# untitled.net
KiCad netlist of a schematic drawn in EAGLE
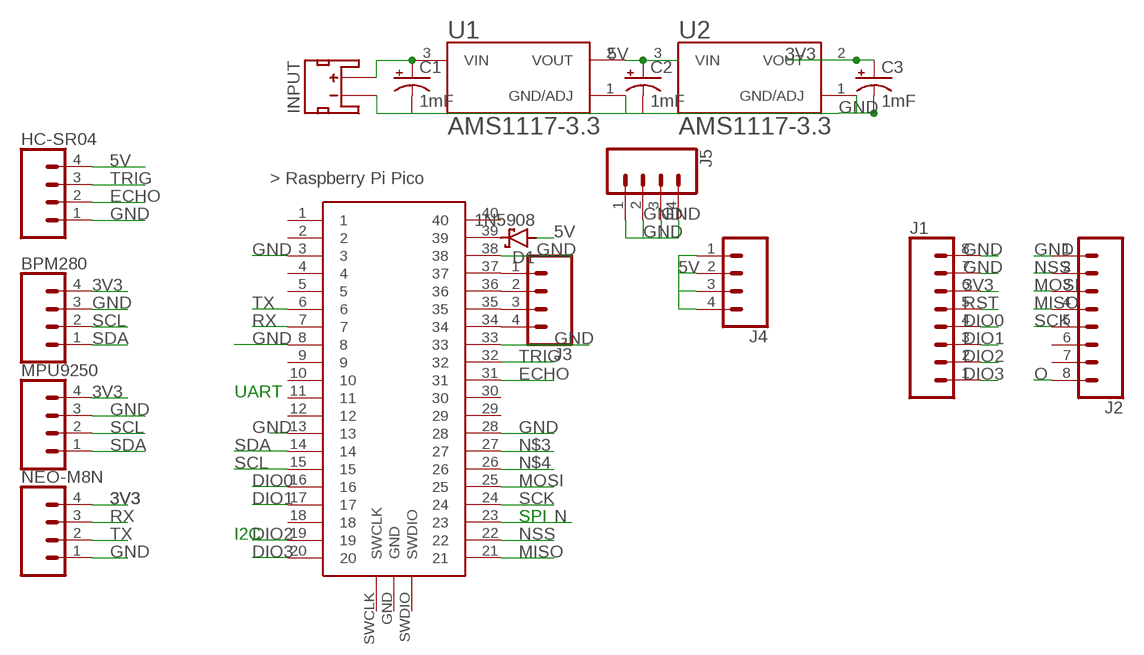
[diagram p0: schematic, sheet 1]

(export (version "E")
  (design (tool "Eeschema 10.0.6"))
  (components
    (comp (ref "BPM280")
      (value "CONN_04PTH")
      (footprint "eagle-import:1X04")
      (libsource (lib "eagle-import") (part "CONN_04PTH"))
    )
    (comp (ref "C1")
      (value "1mF")
      (footprint "eagle-import:CPOL-RADIAL-5MM-10MM")
      (libsource (lib "eagle-import") (part "1000UF-RADIAL-5MM-25V-20%"))
    )
    (comp (ref "C2")
      (value "1mF")
      (footprint "eagle-import:CPOL-RADIAL-5MM-10MM")
      (libsource (lib "eagle-import") (part "1000UF-RADIAL-5MM-25V-20%"))
    )
    (comp (ref "C3")
      (value "1mF")
      (footprint "eagle-import:CPOL-RADIAL-5MM-10MM")
      (libsource (lib "eagle-import") (part "1000UF-RADIAL-5MM-25V-20%"))
    )
    (comp (ref "D1")
      (value "1N5908")
      (footprint "eagle-import:C4111-15")
      (libsource (lib "eagle-import") (part "1N5908"))
    )
    (comp (ref "HC-SR04")
      (value "CONN_04PTH")
      (footprint "eagle-import:1X04")
      (libsource (lib "eagle-import") (part "CONN_04PTH"))
    )
    (comp (ref "INPUT")
      (value "JST_2MM_MALE")
      (footprint "eagle-import:JST-2-SMD")
      (libsource (lib "eagle-import") (part "JST_2MM_MALE"))
    )
    (comp (ref "J1")
      (value "CONN_08NO_SILK_DNP")
      (footprint "eagle-import:1X08_NO_SILK")
      (libsource (lib "eagle-import") (part "CONN_08NO_SILK_DNP"))
    )
    (comp (ref "J2")
      (value "CONN_08NO_SILK_DNP")
      (footprint "eagle-import:1X08_NO_SILK")
      (libsource (lib "eagle-import") (part "CONN_08NO_SILK_DNP"))
    )
    (comp (ref "J3")
      (value "CONN_041X04_NO_SILK")
      (footprint "eagle-import:1X04_NO_SILK")
      (libsource (lib "eagle-import") (part "CONN_041X04_NO_SILK"))
    )
    (comp (ref "J4")
      (value "CONN_041X04_NO_SILK")
      (footprint "eagle-import:1X04_NO_SILK")
      (libsource (lib "eagle-import") (part "CONN_041X04_NO_SILK"))
    )
    (comp (ref "J5")
      (value "CONN_041X04_NO_SILK")
      (footprint "eagle-import:1X04_NO_SILK")
      (libsource (lib "eagle-import") (part "CONN_041X04_NO_SILK"))
    )
    (comp (ref "MPU9250")
      (value "CONN_04PTH")
      (footprint "eagle-import:1X04")
      (libsource (lib "eagle-import") (part "CONN_04PTH"))
    )
    (comp (ref "NEO-M8N")
      (value "CONN_04PTH")
      (footprint "eagle-import:1X04")
      (libsource (lib "eagle-import") (part "CONN_04PTH"))
    )
    (comp (ref "U$1")
      (value "RASPBERRY-PI-PICO_TH")
      (footprint "eagle-import:FT_RASPBERRY-PI-PICO_TH")
      (libsource (lib "eagle-import") (part "RASPBERRY-PI-PICO_TH"))
    )
    (comp (ref "U1")
      (value "AMS1117-3.3")
      (footprint "eagle-import:SOT229P700X180-4N")
      (fields (field (name "MF") "Advanced Monolithic Systems"))
      (libsource (lib "eagle-import") (part "AMS1117-3.3"))
    )
    (comp (ref "U2")
      (value "AMS1117-3.3")
      (footprint "eagle-import:SOT229P700X180-4N")
      (fields (field (name "MF") "Advanced Monolithic Systems"))
      (libsource (lib "eagle-import") (part "AMS1117-3.3"))
    )
  )
  (nets
    (net (code "1") (name "/3V3") (class "Default")
      (node (ref "BPM280") (pin "4") (pinfunction "4_4") (pintype "passive"))
      (node (ref "C3") (pin "+") (pinfunction "+_+") (pintype "passive"))
      (node (ref "J1") (pin "6") (pinfunction "6_6") (pintype "passive"))
      (node (ref "MPU9250") (pin "4") (pinfunction "4_4") (pintype "passive"))
      (node (ref "NEO-M8N") (pin "4") (pinfunction "4_4") (pintype "passive"))
      (node (ref "U2") (pin "2") (pinfunction "VOUT_2") (pintype "output"))
    )
    (net (code "2") (name "/5V") (class "Default")
      (node (ref "C2") (pin "+") (pinfunction "+_+") (pintype "passive"))
      (node (ref "D1") (pin "A") (pinfunction "A_A") (pintype "passive"))
      (node (ref "HC-SR04") (pin "4") (pinfunction "4_4") (pintype "passive"))
      (node (ref "J4") (pin "1") (pinfunction "1_1") (pintype "passive"))
      (node (ref "J4") (pin "2") (pinfunction "2_2") (pintype "passive"))
      (node (ref "J4") (pin "3") (pinfunction "3_3") (pintype "passive"))
      (node (ref "J4") (pin "4") (pinfunction "4_4") (pintype "passive"))
      (node (ref "U1") (pin "2") (pinfunction "VOUT_2") (pintype "output"))
      (node (ref "U2") (pin "3") (pinfunction "VIN_3") (pintype "input"))
    )
    (net (code "3") (name "/DIO0") (class "Default")
      (node (ref "J1") (pin "4") (pinfunction "4_4") (pintype "passive"))
      (node (ref "U$1") (pin "16") (pinfunction "16_16") (pintype "bidirectional"))
    )
    (net (code "4") (name "/DIO1") (class "Default")
      (node (ref "J1") (pin "3") (pinfunction "3_3") (pintype "passive"))
      (node (ref "U$1") (pin "17") (pinfunction "17_17") (pintype "bidirectional"))
    )
    (net (code "5") (name "/DIO2") (class "Default")
      (node (ref "J1") (pin "2") (pinfunction "2_2") (pintype "passive"))
      (node (ref "U$1") (pin "19") (pinfunction "19_19") (pintype "bidirectional"))
    )
    (net (code "6") (name "/DIO3") (class "Default")
      (node (ref "J1") (pin "1") (pinfunction "1_1") (pintype "passive"))
      (node (ref "U$1") (pin "20") (pinfunction "20_20") (pintype "bidirectional"))
    )
    (net (code "7") (name "/ECHO") (class "Default")
      (node (ref "HC-SR04") (pin "2") (pinfunction "2_2") (pintype "passive"))
      (node (ref "U$1") (pin "31") (pinfunction "31_31") (pintype "bidirectional"))
    )
    (net (code "8") (name "/GND") (class "Default")
      (node (ref "BPM280") (pin "3") (pinfunction "3_3") (pintype "passive"))
      (node (ref "C1") (pin "-") (pinfunction "-_-") (pintype "passive"))
      (node (ref "C2") (pin "-") (pinfunction "-_-") (pintype "passive"))
      (node (ref "C3") (pin "-") (pinfunction "-_-") (pintype "passive"))
      (node (ref "HC-SR04") (pin "1") (pinfunction "1_1") (pintype "passive"))
      (node (ref "INPUT") (pin "1") (pinfunction "-_1") (pintype "bidirectional"))
      (node (ref "J1") (pin "7") (pinfunction "7_7") (pintype "passive"))
      (node (ref "J1") (pin "8") (pinfunction "8_8") (pintype "passive"))
      (node (ref "J2") (pin "1") (pinfunction "1_1") (pintype "passive"))
      (node (ref "J5") (pin "1") (pinfunction "1_1") (pintype "passive"))
      (node (ref "J5") (pin "2") (pinfunction "2_2") (pintype "passive"))
      (node (ref "J5") (pin "3") (pinfunction "3_3") (pintype "passive"))
      (node (ref "J5") (pin "4") (pinfunction "4_4") (pintype "passive"))
      (node (ref "MPU9250") (pin "3") (pinfunction "3_3") (pintype "passive"))
      (node (ref "NEO-M8N") (pin "1") (pinfunction "1_1") (pintype "passive"))
      (node (ref "U$1") (pin "13") (pinfunction "13_13") (pintype "bidirectional"))
      (node (ref "U$1") (pin "28") (pinfunction "28_28") (pintype "bidirectional"))
      (node (ref "U$1") (pin "3") (pinfunction "3_3") (pintype "bidirectional"))
      (node (ref "U$1") (pin "33") (pinfunction "33_33") (pintype "bidirectional"))
      (node (ref "U$1") (pin "38") (pinfunction "38_38") (pintype "bidirectional"))
      (node (ref "U$1") (pin "8") (pinfunction "8_8") (pintype "bidirectional"))
      (node (ref "U1") (pin "1") (pinfunction "GND/ADJ_1") (pintype "power_in"))
      (node (ref "U2") (pin "1") (pinfunction "GND/ADJ_1") (pintype "power_in"))
    )
    (net (code "9") (name "/MISO") (class "Default")
      (node (ref "J2") (pin "4") (pinfunction "4_4") (pintype "passive"))
      (node (ref "U$1") (pin "21") (pinfunction "21_21") (pintype "bidirectional"))
    )
    (net (code "10") (name "/MOSI") (class "Default")
      (node (ref "J2") (pin "3") (pinfunction "3_3") (pintype "passive"))
      (node (ref "U$1") (pin "25") (pinfunction "25_25") (pintype "bidirectional"))
    )
    (net (code "11") (name "/N") (class "Default")
      (node (ref "U$1") (pin "23") (pinfunction "23_23") (pintype "bidirectional"))
    )
    (net (code "12") (name "/N$3") (class "Default")
      (node (ref "U$1") (pin "27") (pinfunction "27_27") (pintype "bidirectional"))
    )
    (net (code "13") (name "/N$4") (class "Default")
      (node (ref "U$1") (pin "26") (pinfunction "26_26") (pintype "bidirectional"))
    )
    (net (code "14") (name "/NSS") (class "Default")
      (node (ref "J2") (pin "2") (pinfunction "2_2") (pintype "passive"))
      (node (ref "U$1") (pin "22") (pinfunction "22_22") (pintype "bidirectional"))
    )
    (net (code "15") (name "/O") (class "Default")
      (node (ref "J2") (pin "8") (pinfunction "8_8") (pintype "passive"))
    )
    (net (code "16") (name "/RST") (class "Default")
      (node (ref "J1") (pin "5") (pinfunction "5_5") (pintype "passive"))
    )
    (net (code "17") (name "/RX") (class "Default")
      (node (ref "NEO-M8N") (pin "3") (pinfunction "3_3") (pintype "passive"))
      (node (ref "U$1") (pin "7") (pinfunction "7_7") (pintype "bidirectional"))
    )
    (net (code "18") (name "/SCK") (class "Default")
      (node (ref "J2") (pin "5") (pinfunction "5_5") (pintype "passive"))
      (node (ref "U$1") (pin "24") (pinfunction "24_24") (pintype "bidirectional"))
    )
    (net (code "19") (name "/SCL") (class "Default")
      (node (ref "BPM280") (pin "2") (pinfunction "2_2") (pintype "passive"))
      (node (ref "MPU9250") (pin "2") (pinfunction "2_2") (pintype "passive"))
      (node (ref "U$1") (pin "15") (pinfunction "15_15") (pintype "bidirectional"))
    )
    (net (code "20") (name "/SDA") (class "Default")
      (node (ref "BPM280") (pin "1") (pinfunction "1_1") (pintype "passive"))
      (node (ref "MPU9250") (pin "1") (pinfunction "1_1") (pintype "passive"))
      (node (ref "U$1") (pin "14") (pinfunction "14_14") (pintype "bidirectional"))
    )
    (net (code "21") (name "/TRIG") (class "Default")
      (node (ref "HC-SR04") (pin "3") (pinfunction "3_3") (pintype "passive"))
      (node (ref "U$1") (pin "32") (pinfunction "32_32") (pintype "bidirectional"))
    )
    (net (code "22") (name "/TX") (class "Default")
      (node (ref "NEO-M8N") (pin "2") (pinfunction "2_2") (pintype "passive"))
      (node (ref "U$1") (pin "6") (pinfunction "6_6") (pintype "bidirectional"))
    )
    (net (code "23") (name "Net-(D1-PadC)") (class "Default")
      (node (ref "D1") (pin "C") (pinfunction "C_C") (pintype "passive"))
      (node (ref "U$1") (pin "39") (pinfunction "39_39") (pintype "bidirectional"))
    )
    (net (code "24") (name "Net-(INPUT-+)") (class "Default")
      (node (ref "C1") (pin "+") (pinfunction "+_+") (pintype "passive"))
      (node (ref "INPUT") (pin "2") (pinfunction "+_2") (pintype "bidirectional"))
      (node (ref "U1") (pin "3") (pinfunction "VIN_3") (pintype "input"))
    )
    (net (code "25") (name "Net-(J3-Pad1)") (class "Default")
      (node (ref "J3") (pin "1") (pinfunction "1_1") (pintype "passive"))
      (node (ref "U$1") (pin "37") (pinfunction "37_37") (pintype "bidirectional"))
    )
    (net (code "26") (name "Net-(J3-Pad2)") (class "Default")
      (node (ref "J3") (pin "2") (pinfunction "2_2") (pintype "passive"))
      (node (ref "U$1") (pin "36") (pinfunction "36_36") (pintype "bidirectional"))
    )
    (net (code "27") (name "Net-(J3-Pad3)") (class "Default")
      (node (ref "J3") (pin "3") (pinfunction "3_3") (pintype "passive"))
      (node (ref "U$1") (pin "35") (pinfunction "35_35") (pintype "bidirectional"))
    )
    (net (code "28") (name "Net-(J3-Pad4)") (class "Default")
      (node (ref "J3") (pin "4") (pinfunction "4_4") (pintype "passive"))
      (node (ref "U$1") (pin "34") (pinfunction "34_34") (pintype "bidirectional"))
    )
    (net (code "29") (name "unconnected-(INPUT-PAD1-PadNC1)") (class "Default")
      (node (ref "INPUT") (pin "NC1") (pinfunction "PAD1_NC1") (pintype "bidirectional"))
    )
    (net (code "30") (name "unconnected-(INPUT-PAD2-PadNC2)") (class "Default")
      (node (ref "INPUT") (pin "NC2") (pinfunction "PAD2_NC2") (pintype "bidirectional"))
    )
    (net (code "31") (name "unconnected-(J2-Pad6)") (class "Default")
      (node (ref "J2") (pin "6") (pinfunction "6_6") (pintype "passive"))
    )
    (net (code "32") (name "unconnected-(J2-Pad7)") (class "Default")
      (node (ref "J2") (pin "7") (pinfunction "7_7") (pintype "passive"))
    )
    (net (code "33") (name "unconnected-(U$1-Pad1)") (class "Default")
      (node (ref "U$1") (pin "1") (pinfunction "1_1") (pintype "bidirectional"))
    )
    (net (code "34") (name "unconnected-(U$1-Pad2)") (class "Default")
      (node (ref "U$1") (pin "2") (pinfunction "2_2") (pintype "bidirectional"))
    )
    (net (code "35") (name "unconnected-(U$1-Pad4)") (class "Default")
      (node (ref "U$1") (pin "4") (pinfunction "4_4") (pintype "bidirectional"))
    )
    (net (code "36") (name "unconnected-(U$1-Pad5)") (class "Default")
      (node (ref "U$1") (pin "5") (pinfunction "5_5") (pintype "bidirectional"))
    )
    (net (code "37") (name "unconnected-(U$1-Pad9)") (class "Default")
      (node (ref "U$1") (pin "9") (pinfunction "9_9") (pintype "bidirectional"))
    )
    (net (code "38") (name "unconnected-(U$1-Pad10)") (class "Default")
      (node (ref "U$1") (pin "10") (pinfunction "10_10") (pintype "bidirectional"))
    )
    (net (code "39") (name "unconnected-(U$1-Pad11)") (class "Default")
      (node (ref "U$1") (pin "11") (pinfunction "11_11") (pintype "bidirectional"))
    )
    (net (code "40") (name "unconnected-(U$1-Pad12)") (class "Default")
      (node (ref "U$1") (pin "12") (pinfunction "12_12") (pintype "bidirectional"))
    )
    (net (code "41") (name "unconnected-(U$1-Pad18)") (class "Default")
      (node (ref "U$1") (pin "18") (pinfunction "18_18") (pintype "bidirectional"))
    )
    (net (code "42") (name "unconnected-(U$1-Pad29)") (class "Default")
      (node (ref "U$1") (pin "29") (pinfunction "29_29") (pintype "bidirectional"))
    )
    (net (code "43") (name "unconnected-(U$1-Pad30)") (class "Default")
      (node (ref "U$1") (pin "30") (pinfunction "30_30") (pintype "bidirectional"))
    )
    (net (code "44") (name "unconnected-(U$1-Pad40)") (class "Default")
      (node (ref "U$1") (pin "40") (pinfunction "40_40") (pintype "bidirectional"))
    )
    (net (code "45") (name "unconnected-(U$1-PadGND)") (class "Default")
      (node (ref "U$1") (pin "GND") (pinfunction "GND_GND") (pintype "bidirectional"))
    )
    (net (code "46") (name "unconnected-(U$1-PadSWCLK)") (class "Default")
      (node (ref "U$1") (pin "SWCLK") (pinfunction "SWCLK_SWCLK") (pintype "bidirectional"))
    )
    (net (code "47") (name "unconnected-(U$1-PadSWDIO)") (class "Default")
      (node (ref "U$1") (pin "SWDIO") (pinfunction "SWDIO_SWDIO") (pintype "bidirectional"))
    )
  )
)
